# XKT3619_wireless_charging_driver_T.net
KiCad netlist of a schematic drawn in Altium Designer
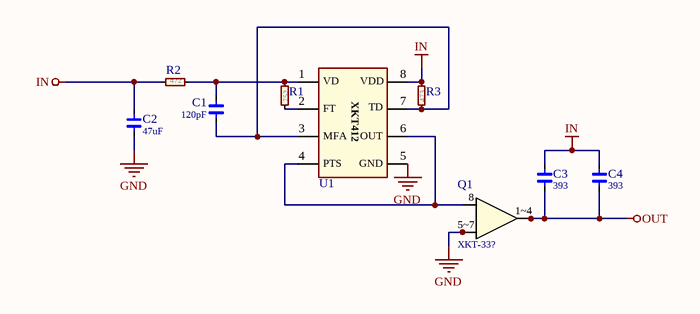
[diagram p0: XKT3619_wireless_charging_driver_T.SchDoc]

(export (version "E")
  (design (tool "Eeschema 10.0.6"))
  (components
    (comp (ref "C1")
      (value "120pF")
      (footprint "CAP_0603")
      (fields (field (name "Comment") "Cap"))
      (libsource (lib "Passive") (part "Cap"))
    )
    (comp (ref "C2")
      (value "47uF")
      (footprint "CAP_1206")
      (fields (field (name "Comment") "Cap"))
      (libsource (lib "Passive") (part "Cap"))
    )
    (comp (ref "C3")
      (value "393")
      (footprint "CAP_1206")
      (fields (field (name "Comment") "Cap"))
      (libsource (lib "Passive") (part "Cap"))
    )
    (comp (ref "C4")
      (value "393")
      (footprint "CAP_1206")
      (fields (field (name "Comment") "Cap"))
      (libsource (lib "Passive") (part "Cap"))
    )
    (comp (ref "Q1")
      (value "XKT-33?")
      (footprint "SOP8_L")
      (fields (field (name "NAME") "XKT-33?"))
      (libsource (lib "Misc") (part "XKT-333/335"))
    )
    (comp (ref "R1")
      (value "752")
      (footprint "RES_0603")
      (fields (field (name "Comment") "Res"))
      (libsource (lib "Passive") (part "Res"))
    )
    (comp (ref "R2")
      (value "472")
      (footprint "RES_0603")
      (fields (field (name "Comment") "Res"))
      (libsource (lib "") (part "Res_1"))
    )
    (comp (ref "R3")
      (value "473")
      (footprint "RES_0603")
      (fields (field (name "Comment") "Res"))
      (libsource (lib "Passive") (part "Res"))
    )
    (comp (ref "U1") (value "XKT-412") (footprint "SOP8_M") (libsource (lib "Misc") (part "XKT-412")))
  )
  (nets
    (net (code "1") (name "GND") (class "Default")
      (node (ref "C2") (pin "2") (pinfunction "2_2") (pintype "passive"))
      (node (ref "Q1") (pin "5") (pinfunction "GND_5") (pintype "passive"))
      (node (ref "Q1") (pin "6") (pinfunction "GND_6") (pintype "passive"))
      (node (ref "Q1") (pin "7") (pinfunction "GND_7") (pintype "passive"))
      (node (ref "U1") (pin "5") (pinfunction "GND_5") (pintype "passive"))
    )
    (net (code "2") (name "IN") (class "Default")
      (node (ref "C2") (pin "1") (pinfunction "1_1") (pintype "passive"))
      (node (ref "C3") (pin "1") (pinfunction "1_1") (pintype "passive"))
      (node (ref "C4") (pin "1") (pinfunction "1_1") (pintype "passive"))
      (node (ref "R2") (pin "1") (pinfunction "1_1") (pintype "passive"))
      (node (ref "R3") (pin "1") (pinfunction "1_1") (pintype "passive"))
      (node (ref "U1") (pin "8") (pinfunction "VDD_8") (pintype "passive"))
    )
    (net (code "3") (name "Net-(Q1-IN)") (class "Default")
      (node (ref "Q1") (pin "8") (pinfunction "IN_8") (pintype "passive"))
      (node (ref "U1") (pin "4") (pinfunction "PTS_4") (pintype "passive"))
      (node (ref "U1") (pin "6") (pinfunction "OUT_6") (pintype "passive"))
    )
    (net (code "4") (name "Net-(U1-FT)") (class "Default")
      (node (ref "R1") (pin "2") (pinfunction "2_2") (pintype "passive"))
      (node (ref "U1") (pin "2") (pinfunction "FT_2") (pintype "passive"))
    )
    (net (code "5") (name "Net-(U1-MFA)") (class "Default")
      (node (ref "C1") (pin "2") (pinfunction "2_2") (pintype "passive"))
      (node (ref "R3") (pin "2") (pinfunction "2_2") (pintype "passive"))
      (node (ref "U1") (pin "3") (pinfunction "MFA_3") (pintype "passive"))
      (node (ref "U1") (pin "7") (pinfunction "TD_7") (pintype "passive"))
    )
    (net (code "6") (name "Net-(U1-VD)") (class "Default")
      (node (ref "C1") (pin "1") (pinfunction "1_1") (pintype "passive"))
      (node (ref "R1") (pin "1") (pinfunction "1_1") (pintype "passive"))
      (node (ref "R2") (pin "2") (pinfunction "2_2") (pintype "passive"))
      (node (ref "U1") (pin "1") (pinfunction "VD_1") (pintype "passive"))
    )
    (net (code "7") (name "OUT") (class "Default")
      (node (ref "C3") (pin "2") (pinfunction "2_2") (pintype "passive"))
      (node (ref "C4") (pin "2") (pinfunction "2_2") (pintype "passive"))
      (node (ref "Q1") (pin "1") (pinfunction "OUT_1") (pintype "passive"))
      (node (ref "Q1") (pin "2") (pinfunction "OUT_2") (pintype "passive"))
      (node (ref "Q1") (pin "3") (pinfunction "OUT_3") (pintype "passive"))
      (node (ref "Q1") (pin "4") (pinfunction "OUT_4") (pintype "passive"))
    )
  )
)
